# RHC12-BTA.net
KiCad netlist of a schematic drawn in EAGLE
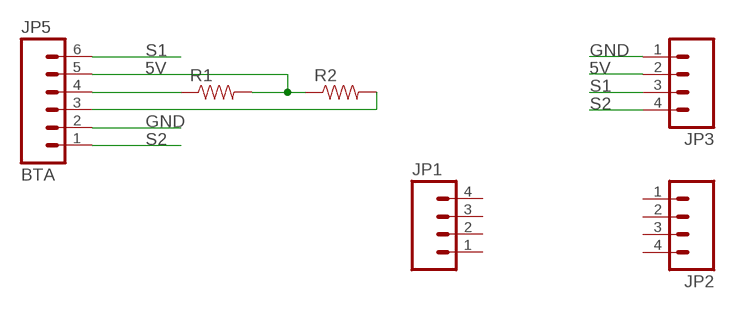
[diagram p0: schematic, sheet 1]

(export (version "E")
  (design (tool "Eeschema 10.0.6"))
  (components
    (comp (ref "JP1")
      (value "M04SMD")
      (footprint "eagle-import:1X04-SMD")
      (libsource (lib "eagle-import") (part "M04SMD"))
    )
    (comp (ref "JP2")
      (value "M04SMD")
      (footprint "eagle-import:1X04-SMD")
      (libsource (lib "eagle-import") (part "M04SMD"))
    )
    (comp (ref "JP3")
      (value "M04SMD")
      (footprint "eagle-import:1X04-SMD")
      (libsource (lib "eagle-import") (part "M04SMD"))
    )
    (comp (ref "JP5")
      (value "BTA")
      (footprint "eagle-import:BTA")
      (libsource (lib "eagle-import") (part "M06VERNIER-ANALOG"))
    )
    (comp (ref "R1")
      (value "RESISTOR0603-RES")
      (footprint "eagle-import:0603-RES")
      (libsource (lib "eagle-import") (part "RESISTOR0603-RES"))
    )
    (comp (ref "R2")
      (value "RESISTOR0603-RES")
      (footprint "eagle-import:0603-RES")
      (libsource (lib "eagle-import") (part "RESISTOR0603-RES"))
    )
  )
  (nets
    (net (code "1") (name "/5V") (class "Default")
      (node (ref "JP3") (pin "2") (pinfunction "2_2") (pintype "passive"))
      (node (ref "JP5") (pin "5") (pinfunction "5_5") (pintype "passive"))
      (node (ref "R1") (pin "2") (pinfunction "2_2") (pintype "passive"))
      (node (ref "R2") (pin "1") (pinfunction "1_1") (pintype "passive"))
    )
    (net (code "2") (name "/GND") (class "Default")
      (node (ref "JP3") (pin "1") (pinfunction "1_1") (pintype "passive"))
      (node (ref "JP5") (pin "2") (pinfunction "2_2") (pintype "passive"))
    )
    (net (code "3") (name "/S1") (class "Default")
      (node (ref "JP3") (pin "3") (pinfunction "3_3") (pintype "passive"))
      (node (ref "JP5") (pin "6") (pinfunction "6_6") (pintype "passive"))
    )
    (net (code "4") (name "/S2") (class "Default")
      (node (ref "JP3") (pin "4") (pinfunction "4_4") (pintype "passive"))
      (node (ref "JP5") (pin "1") (pinfunction "1_1") (pintype "passive"))
    )
    (net (code "5") (name "Net-(JP5-Pad3)") (class "Default")
      (node (ref "JP5") (pin "3") (pinfunction "3_3") (pintype "passive"))
      (node (ref "R2") (pin "2") (pinfunction "2_2") (pintype "passive"))
    )
    (net (code "6") (name "Net-(JP5-Pad4)") (class "Default")
      (node (ref "JP5") (pin "4") (pinfunction "4_4") (pintype "passive"))
      (node (ref "R1") (pin "1") (pinfunction "1_1") (pintype "passive"))
    )
    (net (code "7") (name "unconnected-(JP1-Pad1)") (class "Default")
      (node (ref "JP1") (pin "1") (pinfunction "1_1") (pintype "passive"))
    )
    (net (code "8") (name "unconnected-(JP1-Pad2)") (class "Default")
      (node (ref "JP1") (pin "2") (pinfunction "2_2") (pintype "passive"))
    )
    (net (code "9") (name "unconnected-(JP1-Pad3)") (class "Default")
      (node (ref "JP1") (pin "3") (pinfunction "3_3") (pintype "passive"))
    )
    (net (code "10") (name "unconnected-(JP1-Pad4)") (class "Default")
      (node (ref "JP1") (pin "4") (pinfunction "4_4") (pintype "passive"))
    )
    (net (code "11") (name "unconnected-(JP2-Pad1)") (class "Default")
      (node (ref "JP2") (pin "1") (pinfunction "1_1") (pintype "passive"))
    )
    (net (code "12") (name "unconnected-(JP2-Pad2)") (class "Default")
      (node (ref "JP2") (pin "2") (pinfunction "2_2") (pintype "passive"))
    )
    (net (code "13") (name "unconnected-(JP2-Pad3)") (class "Default")
      (node (ref "JP2") (pin "3") (pinfunction "3_3") (pintype "passive"))
    )
    (net (code "14") (name "unconnected-(JP2-Pad4)") (class "Default")
      (node (ref "JP2") (pin "4") (pinfunction "4_4") (pintype "passive"))
    )
  )
)
